# design.net
KiCad netlist of a schematic drawn in Altium Designer
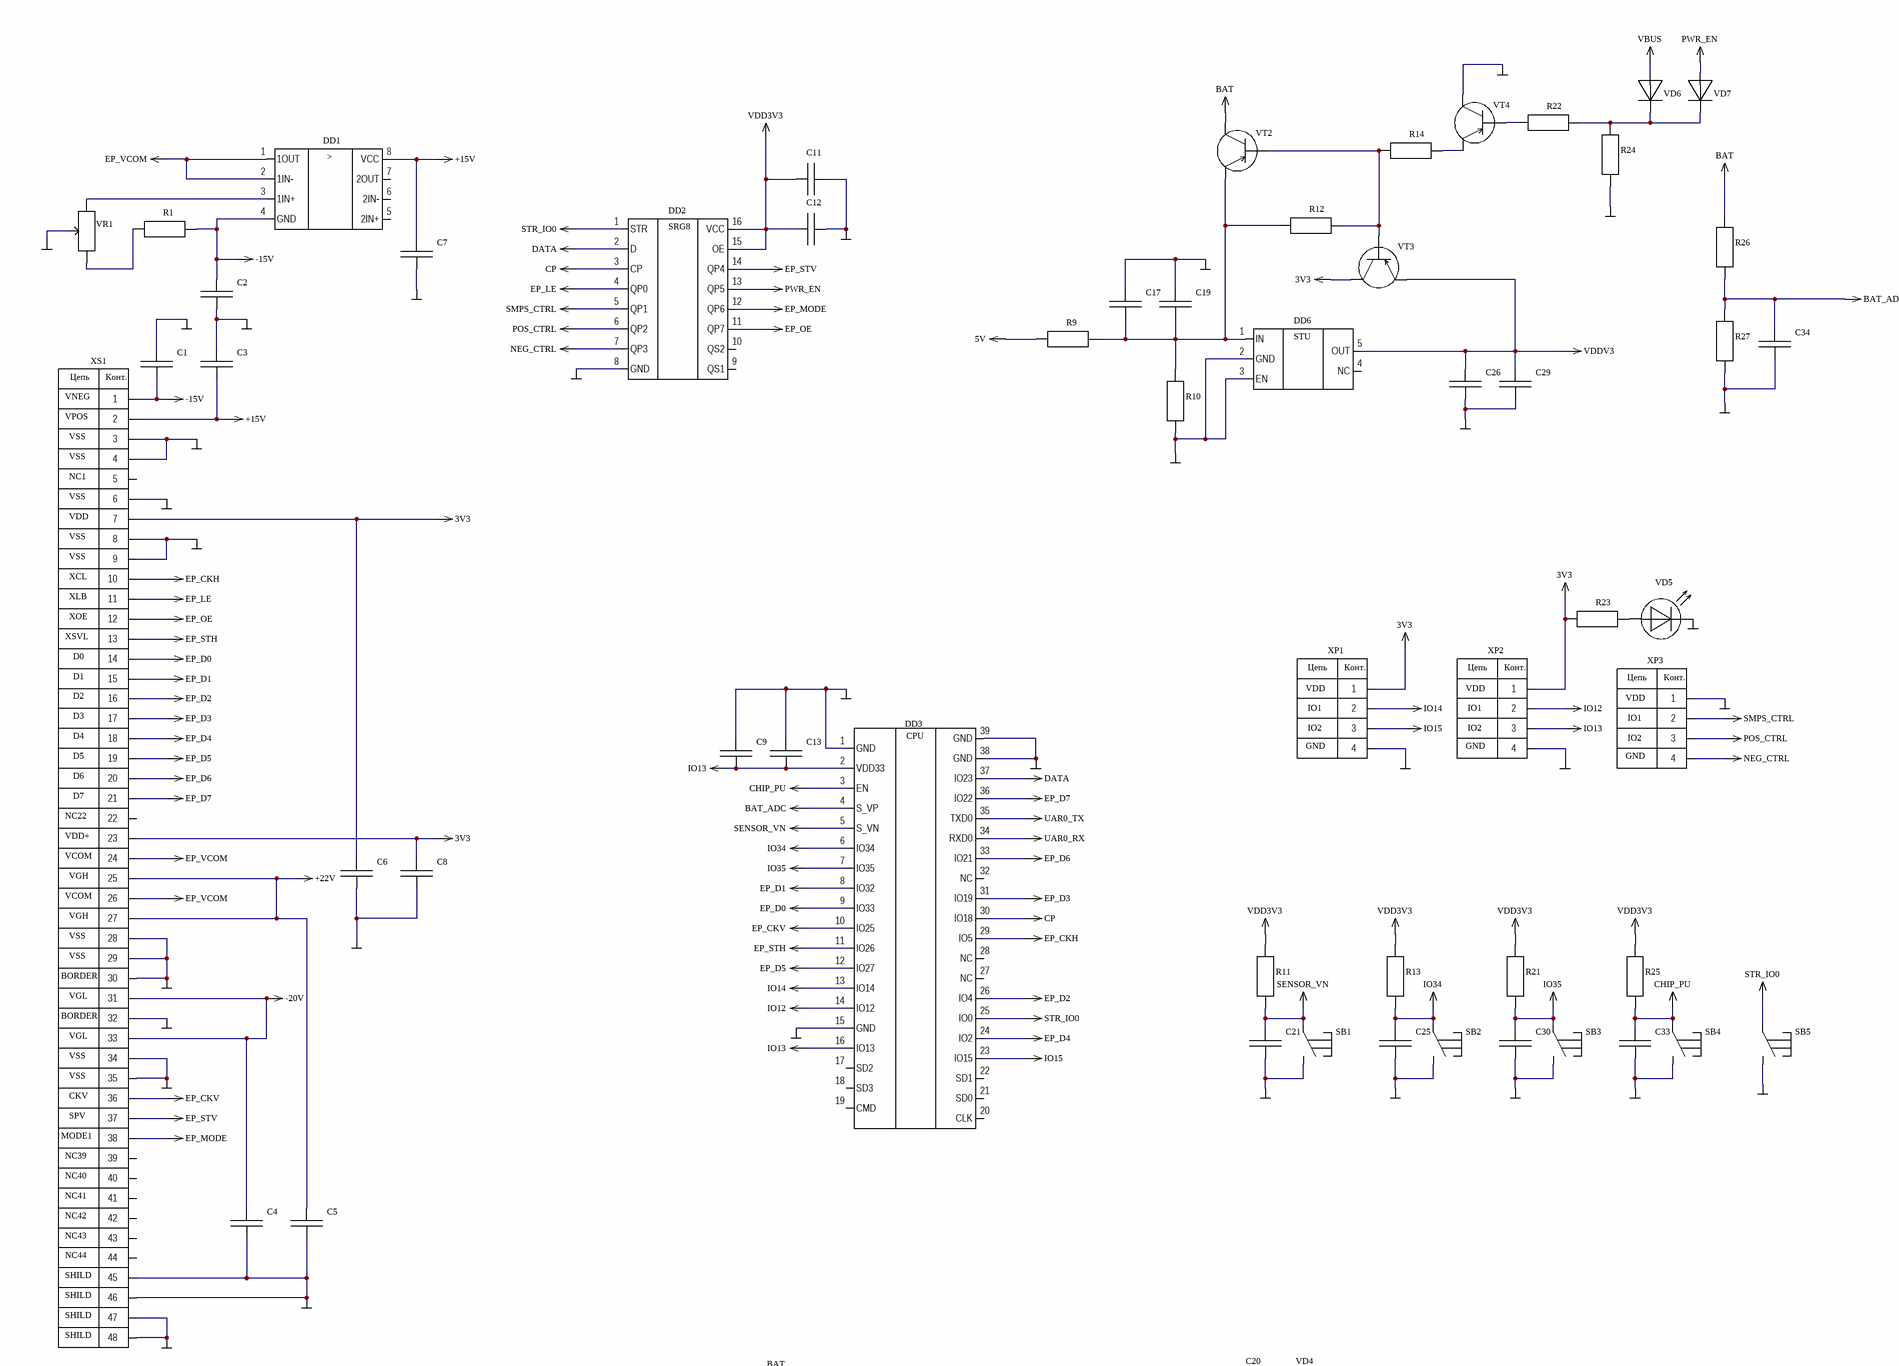
[diagram p0: принципиальная.schdoc, top left]
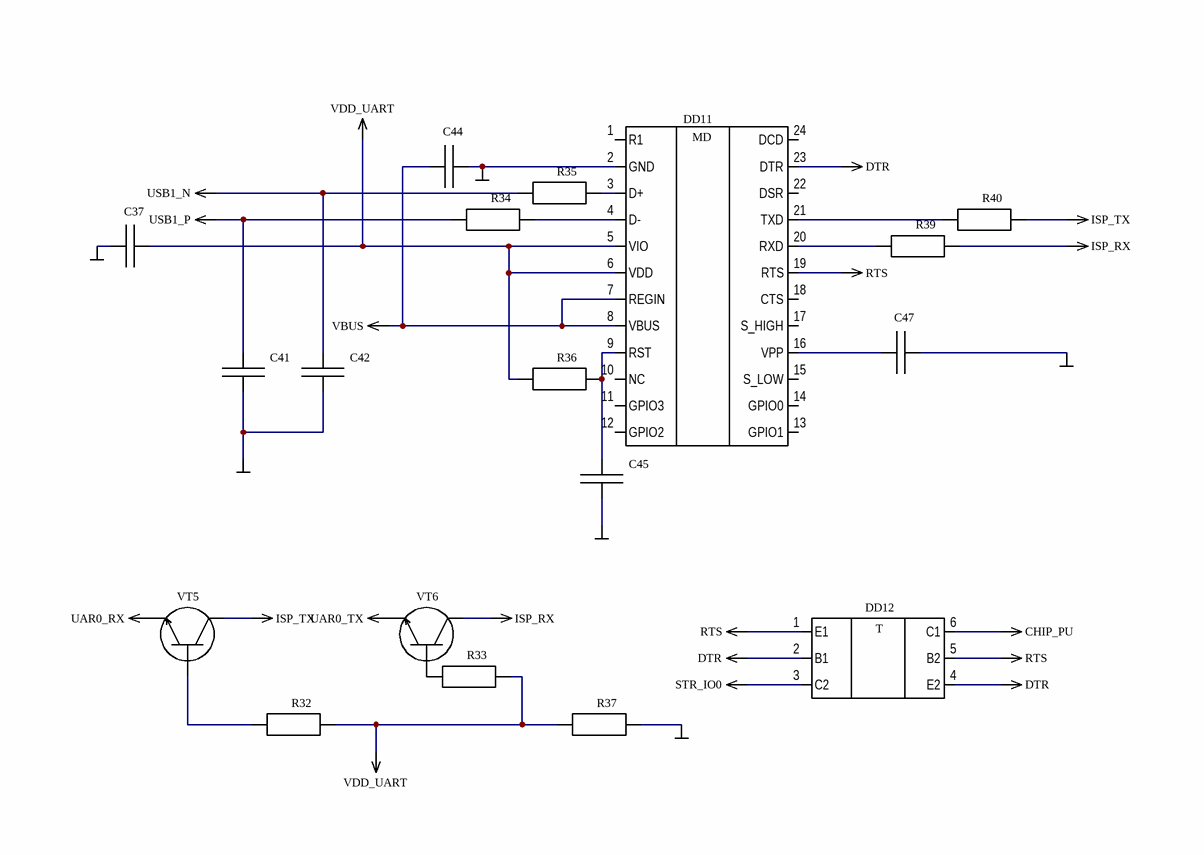
[diagram p1: принципиальная.schdoc, top right]
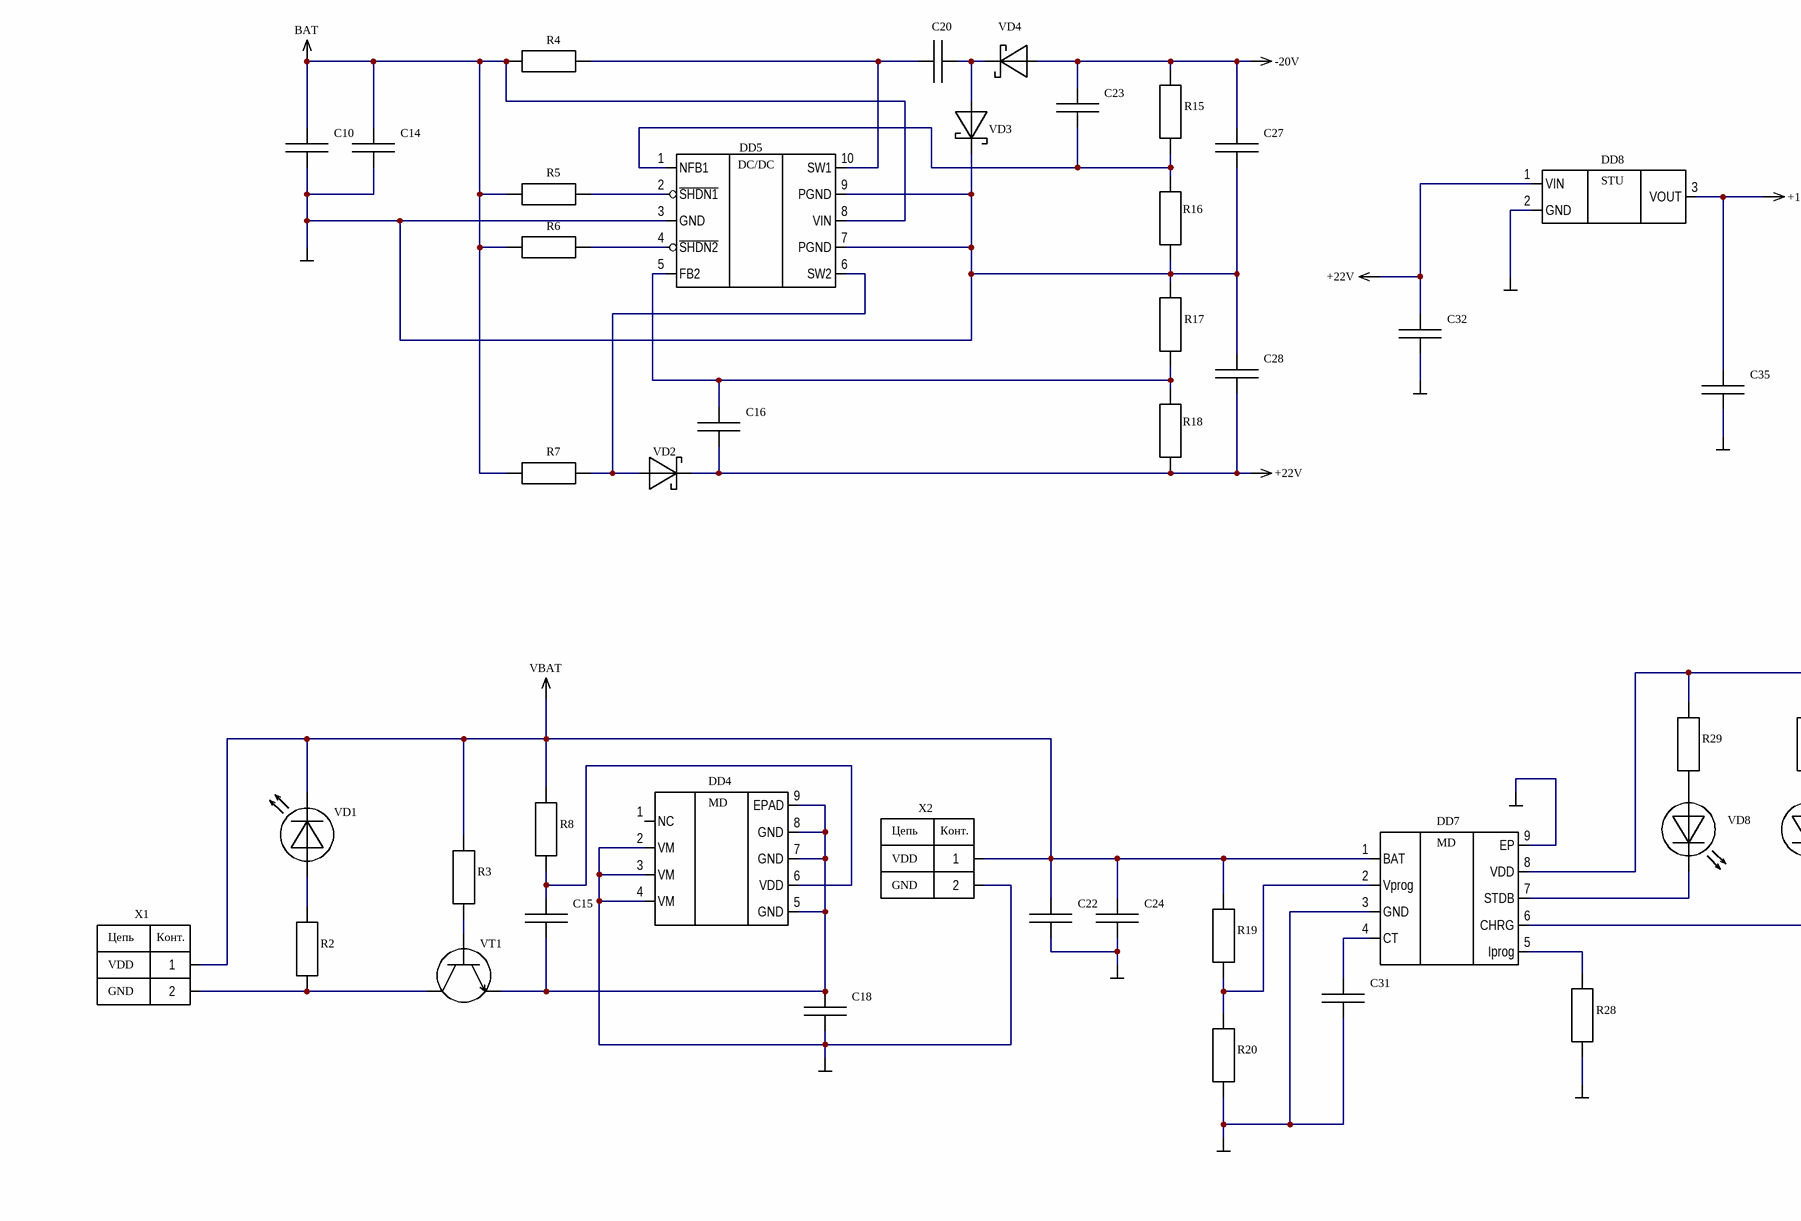
[diagram p2: принципиальная.schdoc, bottom left]
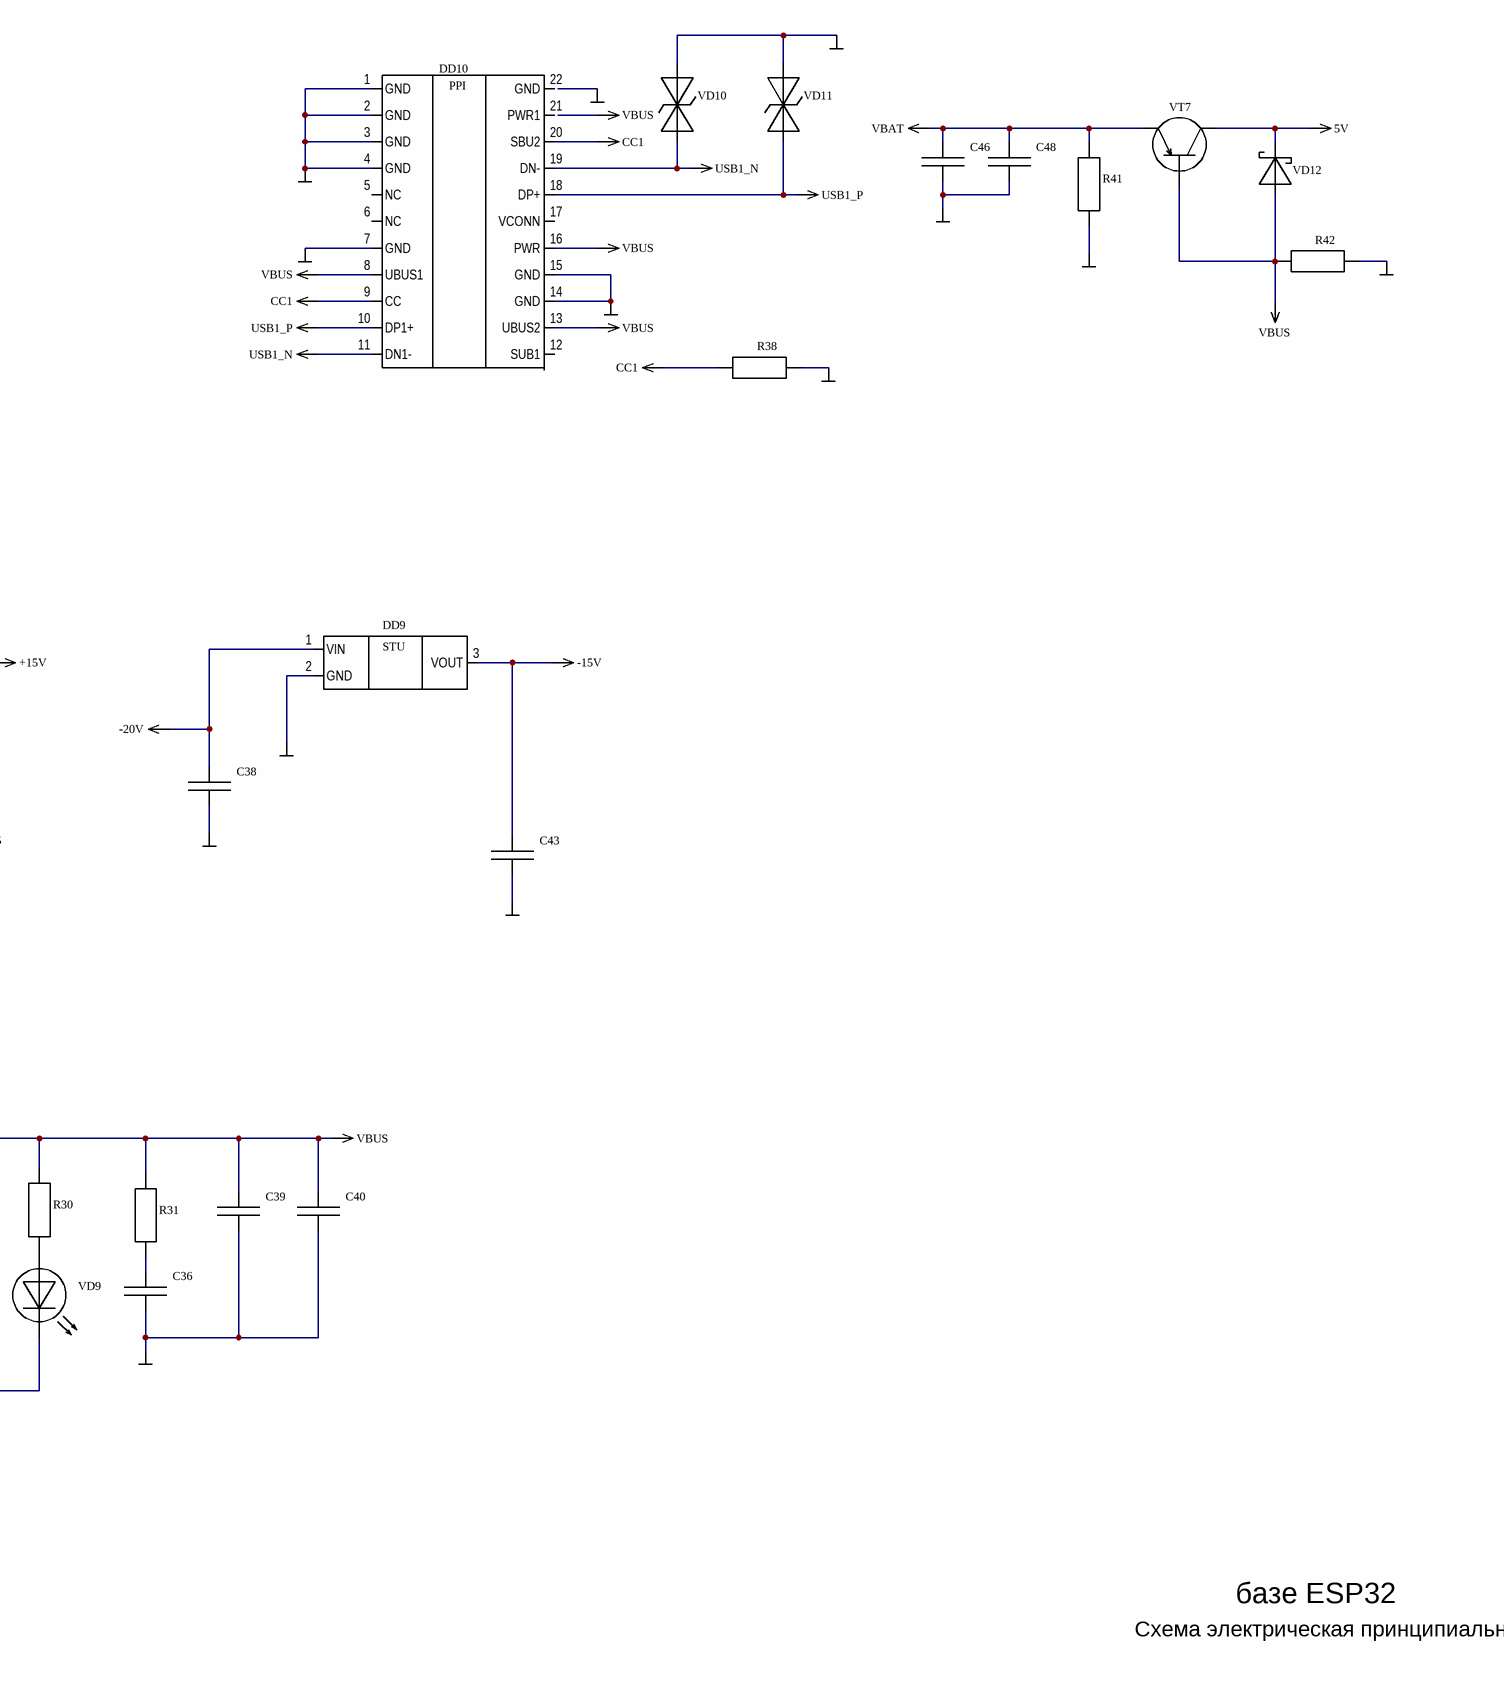
[diagram p3: принципиальная.schdoc, bottom right]

(export (version "E")
  (design (tool "Eeschema 10.0.6"))
  (components
    (comp (ref "C1")
      (value "Capacitor")
      (footprint "condensator CAP3216X125N:CAP3216X125N")
      (libsource (lib "Library_ugo") (part "Capacitor"))
    )
    (comp (ref "C2")
      (value "Capacitor")
      (footprint "condensator CAP3216X125N:CAP3216X125N")
      (libsource (lib "Library_ugo") (part "Capacitor"))
    )
    (comp (ref "C3")
      (value "Capacitor")
      (footprint "condensator CAP3216X125N:CAP3216X125N")
      (libsource (lib "Library_ugo") (part "Capacitor"))
    )
    (comp (ref "C4")
      (value "Capacitor")
      (footprint "condensator CAP3216X125N:CAP3216X125N")
      (libsource (lib "Library_ugo") (part "Capacitor"))
    )
    (comp (ref "C5")
      (value "Capacitor")
      (footprint "condensator CAP3216X125N:CAP3216X125N")
      (libsource (lib "Library_ugo") (part "Capacitor"))
    )
    (comp (ref "C6")
      (value "Capacitor")
      (footprint "condensator CAP3216X125N:CAP3216X125N")
      (libsource (lib "Library_ugo") (part "Capacitor"))
    )
    (comp (ref "C7")
      (value "Capacitor")
      (footprint "condensator CAP3216X125N:CAP3216X125N")
      (libsource (lib "Library_ugo") (part "Capacitor"))
    )
    (comp (ref "C8")
      (value "Capacitor")
      (footprint "condensator CAP3216X125N:CAP3216X125N")
      (libsource (lib "Library_ugo") (part "Capacitor"))
    )
    (comp (ref "C9")
      (value "Capacitor")
      (footprint "condensator CAP3216X125N:CAP3216X125N")
      (libsource (lib "Library_ugo") (part "Capacitor"))
    )
    (comp (ref "C10")
      (value "Capacitor")
      (footprint "condensator CAP3216X125N:CAP3216X125N")
      (libsource (lib "Library_ugo") (part "Capacitor"))
    )
    (comp (ref "C11")
      (value "Capacitor")
      (footprint "condensator CAP3216X125N:CAP3216X125N")
      (libsource (lib "Library_ugo") (part "Capacitor"))
    )
    (comp (ref "C12")
      (value "Capacitor")
      (footprint "condensator CAP3216X125N:CAP3216X125N")
      (libsource (lib "Library_ugo") (part "Capacitor"))
    )
    (comp (ref "C13")
      (value "Capacitor")
      (footprint "condensator CAP3216X125N:CAP3216X125N")
      (libsource (lib "Library_ugo") (part "Capacitor"))
    )
    (comp (ref "C14")
      (value "Capacitor")
      (footprint "condensator CAP3216X125N:CAP3216X125N")
      (libsource (lib "Library_ugo") (part "Capacitor"))
    )
    (comp (ref "C15")
      (value "Capacitor")
      (footprint "condensator CAP3216X125N:CAP3216X125N")
      (libsource (lib "Library_ugo") (part "Capacitor"))
    )
    (comp (ref "C16")
      (value "Capacitor")
      (footprint "condensator CAP3216X125N:CAP3216X125N")
      (libsource (lib "Library_ugo") (part "Capacitor"))
    )
    (comp (ref "C17")
      (value "Capacitor")
      (footprint "condensator CAP3216X125N:CAP3216X125N")
      (libsource (lib "Library_ugo") (part "Capacitor"))
    )
    (comp (ref "C18")
      (value "Capacitor")
      (footprint "condensator CAP3216X125N:CAP3216X125N")
      (libsource (lib "Library_ugo") (part "Capacitor"))
    )
    (comp (ref "C19")
      (value "Capacitor")
      (footprint "condensator CAP3216X125N:CAP3216X125N")
      (libsource (lib "Library_ugo") (part "Capacitor"))
    )
    (comp (ref "C20")
      (value "Capacitor")
      (footprint "condensator CAP3216X125N:CAP3216X125N")
      (libsource (lib "Library_ugo") (part "Capacitor"))
    )
    (comp (ref "C21")
      (value "Capacitor")
      (footprint "condensator CAP3216X125N:CAP3216X125N")
      (libsource (lib "Library_ugo") (part "Capacitor"))
    )
    (comp (ref "C22")
      (value "Capacitor")
      (footprint "condensator CAP3216X125N:CAP3216X125N")
      (libsource (lib "Library_ugo") (part "Capacitor"))
    )
    (comp (ref "C23")
      (value "Capacitor")
      (footprint "condensator CAP3216X125N:CAP3216X125N")
      (libsource (lib "Library_ugo") (part "Capacitor"))
    )
    (comp (ref "C24")
      (value "Capacitor")
      (footprint "condensator CAP3216X125N:CAP3216X125N")
      (libsource (lib "Library_ugo") (part "Capacitor"))
    )
    (comp (ref "C25")
      (value "Capacitor")
      (footprint "condensator CAP3216X125N:CAP3216X125N")
      (libsource (lib "Library_ugo") (part "Capacitor"))
    )
    (comp (ref "C26")
      (value "Capacitor")
      (footprint "condensator CAP3216X125N:CAP3216X125N")
      (libsource (lib "Library_ugo") (part "Capacitor"))
    )
    (comp (ref "C27")
      (value "Capacitor")
      (footprint "condensator CAP3216X125N:CAP3216X125N")
      (libsource (lib "Library_ugo") (part "Capacitor"))
    )
    (comp (ref "C28")
      (value "Capacitor")
      (footprint "condensator CAP3216X125N:CAP3216X125N")
      (libsource (lib "Library_ugo") (part "Capacitor"))
    )
    (comp (ref "C29")
      (value "Capacitor")
      (footprint "condensator CAP3216X125N:CAP3216X125N")
      (libsource (lib "Library_ugo") (part "Capacitor"))
    )
    (comp (ref "C30")
      (value "Capacitor")
      (footprint "condensator CAP3216X125N:CAP3216X125N")
      (libsource (lib "Library_ugo") (part "Capacitor"))
    )
    (comp (ref "C31")
      (value "Capacitor")
      (footprint "condensator CAP3216X125N:CAP3216X125N")
      (libsource (lib "Library_ugo") (part "Capacitor"))
    )
    (comp (ref "C32")
      (value "Capacitor")
      (footprint "condensator CAP3216X125N:CAP3216X125N")
      (libsource (lib "Library_ugo") (part "Capacitor"))
    )
    (comp (ref "C33")
      (value "Capacitor")
      (footprint "condensator CAP3216X125N:CAP3216X125N")
      (libsource (lib "Library_ugo") (part "Capacitor"))
    )
    (comp (ref "C34")
      (value "Capacitor")
      (footprint "condensator CAP3216X125N:CAP3216X125N")
      (libsource (lib "Library_ugo") (part "Capacitor"))
    )
    (comp (ref "C35")
      (value "Capacitor")
      (footprint "condensator CAP3216X125N:CAP3216X125N")
      (libsource (lib "Library_ugo") (part "Capacitor"))
    )
    (comp (ref "C36")
      (value "Capacitor")
      (footprint "condensator CAP3216X125N:CAP3216X125N")
      (libsource (lib "Library_ugo") (part "Capacitor"))
    )
    (comp (ref "C37")
      (value "Capacitor")
      (footprint "condensator CAP3216X125N:CAP3216X125N")
      (libsource (lib "Library_ugo") (part "Capacitor"))
    )
    (comp (ref "C38")
      (value "Capacitor")
      (footprint "condensator CAP3216X125N:CAP3216X125N")
      (libsource (lib "Library_ugo") (part "Capacitor"))
    )
    (comp (ref "C39")
      (value "Capacitor")
      (footprint "condensator CAP3216X125N:CAP3216X125N")
      (libsource (lib "Library_ugo") (part "Capacitor"))
    )
    (comp (ref "C40")
      (value "Capacitor")
      (footprint "condensator CAP3216X125N:CAP3216X125N")
      (libsource (lib "Library_ugo") (part "Capacitor"))
    )
    (comp (ref "C41")
      (value "Capacitor")
      (footprint "condensator CAP3216X125N:CAP3216X125N")
      (libsource (lib "Library_ugo") (part "Capacitor"))
    )
    (comp (ref "C42")
      (value "Capacitor")
      (footprint "condensator CAP3216X125N:CAP3216X125N")
      (libsource (lib "Library_ugo") (part "Capacitor"))
    )
    (comp (ref "C43")
      (value "Capacitor")
      (footprint "condensator CAP3216X125N:CAP3216X125N")
      (libsource (lib "Library_ugo") (part "Capacitor"))
    )
    (comp (ref "C44")
      (value "Capacitor")
      (footprint "condensator CAP3216X125N:CAP3216X125N")
      (libsource (lib "Library_ugo") (part "Capacitor"))
    )
    (comp (ref "C45")
      (value "Capacitor")
      (footprint "condensator CAP3216X125N:CAP3216X125N")
      (libsource (lib "Library_ugo") (part "Capacitor"))
    )
    (comp (ref "C46")
      (value "Capacitor")
      (footprint "condensator CAP3216X125N:CAP3216X125N")
      (libsource (lib "Library_ugo") (part "Capacitor"))
    )
    (comp (ref "C47")
      (value "Capacitor")
      (footprint "condensator CAP3216X125N:CAP3216X125N")
      (libsource (lib "Library_ugo") (part "Capacitor"))
    )
    (comp (ref "C48")
      (value "Capacitor")
      (footprint "condensator CAP3216X125N:CAP3216X125N")
      (libsource (lib "Library_ugo") (part "Capacitor"))
    )
    (comp (ref "DD1")
      (value "LM358DR2G")
      (footprint "SOIC127P599X175-8N:SOIC127P599X175-8N")
      (libsource (lib "Library_ugo") (part "LM358DR2G"))
    )
    (comp (ref "DD2")
      (value "74HCT4094D")
      (footprint "SOIC127P1030X265-16N:SOIC127P1030X265-16N")
      (libsource (lib "Library_ugo") (part "74HCT4094D"))
    )
    (comp (ref "DD3")
      (value "ESP32-WROVER-E")
      (footprint "SnapEDApcb:XCVR_ESP32-WROVER")
      (libsource (lib "Library_ugo") (part "ESP32-WROVER-E"))
    )
    (comp (ref "DD4")
      (value "IP3005A")
      (footprint "SI2301:ESOP-8_L4.9-W3.9-P1.27-LS6.0-BL-EP")
      (libsource (lib "Library_ugo") (part "IP3005A"))
    )
    (comp (ref "DD5")
      (value "LT1945")
      (footprint "MSOP-10_MS:MSOP-10_MS")
      (libsource (lib "Library_ugo") (part "LT1945"))
    )
    (comp (ref "DD6")
      (value "AP2112K")
      (footprint "SnapEDApcb:SOT95P280X145-5N")
      (libsource (lib "Library_ugo") (part "AP2112K"))
    )
    (comp (ref "DD7")
      (value "HX6610S")
      (footprint "SI2301:ESOP-8_L4.9-W3.9-P1.27-LS6.0-BL-EP")
      (libsource (lib "Library_ugo") (part "HX6610S"))
    )
    (comp (ref "DD8")
      (value "CJ78L15")
      (footprint "SnapEDApcb:REG_MCP1702T-3302E/MB")
      (libsource (lib "Library_ugo") (part "CJ78L15"))
    )
    (comp (ref "DD9")
      (value "CJ78L15")
      (footprint "SnapEDApcb:REG_MCP1702T-3302E/MB")
      (libsource (lib "Library_ugo") (part "CJ78L15"))
    )
    (comp (ref "DD10")
      (value "TYPE C")
      (footprint "SnapEDApcb:QFN50P400X400X80-25N")
      (libsource (lib "Library_ugo") (part "TYPE C"))
    )
    (comp (ref "DD11")
      (value "CP2014")
      (footprint "SnapEDApcb:QFN50P400X400X80-25N")
      (libsource (lib "Library_ugo") (part "CP2014"))
    )
    (comp (ref "DD12")
      (value "UMH3N")
      (footprint "SnapEDApcb:SOP65P210X100-6N")
      (libsource (lib "Library_ugo") (part "UMH3N"))
    )
    (comp (ref "R1")
      (value "Resistor")
      (footprint "Library_footprint:res0603")
      (libsource (lib "Library_ugo") (part "Resistor"))
    )
    (comp (ref "R2")
      (value "Resistor")
      (footprint "Library_footprint:res0603")
      (libsource (lib "Library_ugo") (part "Resistor"))
    )
    (comp (ref "R3")
      (value "Resistor")
      (footprint "Library_footprint:res0603")
      (libsource (lib "Library_ugo") (part "Resistor"))
    )
    (comp (ref "R4")
      (value "Resistor")
      (footprint "Library_footprint:res0603")
      (libsource (lib "Library_ugo") (part "Resistor"))
    )
    (comp (ref "R5")
      (value "Resistor")
      (footprint "Library_footprint:res0603")
      (libsource (lib "Library_ugo") (part "Resistor"))
    )
    (comp (ref "R6")
      (value "Resistor")
      (footprint "Library_footprint:res0603")
      (libsource (lib "Library_ugo") (part "Resistor"))
    )
    (comp (ref "R7")
      (value "Resistor")
      (footprint "Library_footprint:res0603")
      (libsource (lib "Library_ugo") (part "Resistor"))
    )
    (comp (ref "R8")
      (value "Resistor")
      (footprint "Library_footprint:res0603")
      (libsource (lib "Library_ugo") (part "Resistor"))
    )
    (comp (ref "R9")
      (value "Resistor")
      (footprint "Library_footprint:res0603")
      (libsource (lib "Library_ugo") (part "Resistor"))
    )
    (comp (ref "R10")
      (value "Resistor")
      (footprint "Library_footprint:res0603")
      (libsource (lib "Library_ugo") (part "Resistor"))
    )
    (comp (ref "R11")
      (value "Resistor")
      (footprint "Library_footprint:res0603")
      (libsource (lib "Library_ugo") (part "Resistor"))
    )
    (comp (ref "R12")
      (value "Resistor")
      (footprint "Library_footprint:res0603")
      (libsource (lib "Library_ugo") (part "Resistor"))
    )
    (comp (ref "R13")
      (value "Resistor")
      (footprint "Library_footprint:res0603")
      (libsource (lib "Library_ugo") (part "Resistor"))
    )
    (comp (ref "R14")
      (value "Resistor")
      (footprint "Library_footprint:res0603")
      (libsource (lib "Library_ugo") (part "Resistor"))
    )
    (comp (ref "R15")
      (value "Resistor")
      (footprint "Library_footprint:res0603")
      (libsource (lib "Library_ugo") (part "Resistor"))
    )
    (comp (ref "R16")
      (value "Resistor")
      (footprint "Library_footprint:res0603")
      (libsource (lib "Library_ugo") (part "Resistor"))
    )
    (comp (ref "R17")
      (value "Resistor")
      (footprint "Library_footprint:res0603")
      (libsource (lib "Library_ugo") (part "Resistor"))
    )
    (comp (ref "R18")
      (value "Resistor")
      (footprint "Library_footprint:res0603")
      (libsource (lib "Library_ugo") (part "Resistor"))
    )
    (comp (ref "R19")
      (value "Resistor")
      (footprint "Library_footprint:res0603")
      (libsource (lib "Library_ugo") (part "Resistor"))
    )
    (comp (ref "R20")
      (value "Resistor")
      (footprint "Library_footprint:res0603")
      (libsource (lib "Library_ugo") (part "Resistor"))
    )
    (comp (ref "R21")
      (value "Resistor")
      (footprint "Library_footprint:res0603")
      (libsource (lib "Library_ugo") (part "Resistor"))
    )
    (comp (ref "R22")
      (value "Resistor")
      (footprint "Library_footprint:res0603")
      (libsource (lib "Library_ugo") (part "Resistor"))
    )
    (comp (ref "R23")
      (value "Resistor")
      (footprint "Library_footprint:res0603")
      (libsource (lib "Library_ugo") (part "Resistor"))
    )
    (comp (ref "R24")
      (value "Resistor")
      (footprint "Library_footprint:res0603")
      (libsource (lib "Library_ugo") (part "Resistor"))
    )
    (comp (ref "R25")
      (value "Resistor")
      (footprint "Library_footprint:res0603")
      (libsource (lib "Library_ugo") (part "Resistor"))
    )
    (comp (ref "R26")
      (value "Resistor")
      (footprint "Library_footprint:res0603")
      (libsource (lib "Library_ugo") (part "Resistor"))
    )
    (comp (ref "R27")
      (value "Resistor")
      (footprint "Library_footprint:res0603")
      (libsource (lib "Library_ugo") (part "Resistor"))
    )
    (comp (ref "R28")
      (value "Resistor")
      (footprint "Library_footprint:res0603")
      (libsource (lib "Library_ugo") (part "Resistor"))
    )
    (comp (ref "R29")
      (value "Resistor")
      (footprint "Library_footprint:res0603")
      (libsource (lib "Library_ugo") (part "Resistor"))
    )
    (comp (ref "R30")
      (value "Resistor")
      (footprint "Library_footprint:res0603")
      (libsource (lib "Library_ugo") (part "Resistor"))
    )
    (comp (ref "R31")
      (value "Resistor")
      (footprint "Library_footprint:res0603")
      (libsource (lib "Library_ugo") (part "Resistor"))
    )
    (comp (ref "R32")
      (value "Resistor")
      (footprint "Library_footprint:res0603")
      (libsource (lib "Library_ugo") (part "Resistor"))
    )
    (comp (ref "R33")
      (value "Resistor")
      (footprint "Library_footprint:res0603")
      (libsource (lib "Library_ugo") (part "Resistor"))
    )
    (comp (ref "R34")
      (value "Resistor")
      (footprint "Library_footprint:res0603")
      (libsource (lib "Library_ugo") (part "Resistor"))
    )
    (comp (ref "R35")
      (value "Resistor")
      (footprint "Library_footprint:res0603")
      (libsource (lib "Library_ugo") (part "Resistor"))
    )
    (comp (ref "R36")
      (value "Resistor")
      (footprint "Library_footprint:res0603")
      (libsource (lib "Library_ugo") (part "Resistor"))
    )
    (comp (ref "R37")
      (value "Resistor")
      (footprint "Library_footprint:res0603")
      (libsource (lib "Library_ugo") (part "Resistor"))
    )
    (comp (ref "R38")
      (value "Resistor")
      (footprint "Library_footprint:res0603")
      (libsource (lib "Library_ugo") (part "Resistor"))
    )
    (comp (ref "R39")
      (value "Resistor")
      (footprint "Library_footprint:res0603")
      (libsource (lib "Library_ugo") (part "Resistor"))
    )
    (comp (ref "R40")
      (value "Resistor")
      (footprint "Library_footprint:res0603")
      (libsource (lib "Library_ugo") (part "Resistor"))
    )
    (comp (ref "R41")
      (value "Resistor")
      (footprint "Library_footprint:res0603")
      (libsource (lib "Library_ugo") (part "Resistor"))
    )
    (comp (ref "R42")
      (value "Resistor")
      (footprint "Library_footprint:res0603")
      (libsource (lib "Library_ugo") (part "Resistor"))
    )
    (comp (ref "SB1")
      (value "button")
      (footprint "SnapEDApcb:SW_147873-1")
      (libsource (lib "Library_ugo") (part "button"))
    )
    (comp (ref "SB2")
      (value "button")
      (footprint "SnapEDApcb:SW_147873-1")
      (libsource (lib "Library_ugo") (part "button"))
    )
    (comp (ref "SB3")
      (value "button")
      (footprint "SnapEDApcb:SW_147873-1")
      (libsource (lib "Library_ugo") (part "button"))
    )
    (comp (ref "SB4")
      (value "button")
      (footprint "SnapEDApcb:SW_147873-1")
      (libsource (lib "Library_ugo") (part "button"))
    )
    (comp (ref "SB5")
      (value "button")
      (footprint "SnapEDApcb:SW_147873-1")
      (libsource (lib "Library_ugo") (part "button"))
    )
    (comp (ref "VD1")
      (value "LED diode")
      (footprint "led diode:BEADC0603X33N")
      (libsource (lib "Library_ugo") (part "LED diode"))
    )
    (comp (ref "VD2")
      (value "1N5819")
      (footprint "SOD3715X145N:SOD3715X145N")
      (libsource (lib "Library_ugo") (part "1N5819"))
    )
    (comp (ref "VD3")
      (value "1N5819")
      (footprint "SOD3715X145N:SOD3715X145N")
      (libsource (lib "Library_ugo") (part "1N5819"))
    )
    (comp (ref "VD4")
      (value "1N5819")
      (footprint "SOD3715X145N:SOD3715X145N")
      (libsource (lib "Library_ugo") (part "1N5819"))
    )
    (comp (ref "VD5")
      (value "LED diode")
      (footprint "led diode:BEADC0603X33N")
      (libsource (lib "Library_ugo") (part "LED diode"))
    )
    (comp (ref "VD6")
      (value "Diod")
      (footprint "SnapEDApcb:SODFL1608X70N")
      (libsource (lib "Library_ugo") (part "Diod"))
    )
    (comp (ref "VD7")
      (value "Diod")
      (footprint "SnapEDApcb:SODFL1608X70N")
      (libsource (lib "Library_ugo") (part "Diod"))
    )
    (comp (ref "VD8")
      (value "LED diode")
      (footprint "led diode:BEADC0603X33N")
      (libsource (lib "Library_ugo") (part "LED diode"))
    )
    (comp (ref "VD9")
      (value "LED diode")
      (footprint "led diode:BEADC0603X33N")
      (libsource (lib "Library_ugo") (part "LED diode"))
    )
    (comp (ref "VD10")
      (value "ESD diode")
      (footprint "SnapEDApcb:SOD523")
      (libsource (lib "Library_ugo") (part "ESD diode"))
    )
    (comp (ref "VD11")
      (value "ESD diode")
      (footprint "SnapEDApcb:SOD523")
      (libsource (lib "Library_ugo") (part "ESD diode"))
    )
    (comp (ref "VD12")
      (value "1N5819")
      (footprint "SOD3715X145N:SOD3715X145N")
      (libsource (lib "Library_ugo") (part "1N5819"))
    )
    (comp (ref "VR1")
      (value "TRIMPOT-SMD-3MM")
      (footprint "SOIC127P599X175-8N:TRIMPOT-SMD-TC33X")
      (libsource (lib "Library_ugo") (part "TRIMPOT-SMD-3MM"))
    )
    (comp (ref "VT1")
      (value "Transistor(npn)")
      (footprint "SI2301:SOT23-3P96_237X112L42X44")
      (libsource (lib "Library_ugo") (part "Transistor(npn)"))
    )
    (comp (ref "VT2")
      (value "Transistor(pnp)")
      (footprint "SI2301:SOT23-3P96_237X112L42X44")
      (libsource (lib "Library_ugo") (part "Transistor(pnp)"))
    )
    (comp (ref "VT3")
      (value "Transistor(pnp)")
      (footprint "SI2301:SOT23-3P96_237X112L42X44")
      (libsource (lib "Library_ugo") (part "Transistor(pnp)"))
    )
    (comp (ref "VT4")
      (value "Transistor(pnp)")
      (footprint "SI2301:SOT23-3P96_237X112L42X44")
      (libsource (lib "Library_ugo") (part "Transistor(pnp)"))
    )
    (comp (ref "VT5")
      (value "Transistor(npn)")
      (footprint "SI2301:SOT23-3P96_237X112L42X44")
      (libsource (lib "Library_ugo") (part "Transistor(npn)"))
    )
    (comp (ref "VT6")
      (value "Transistor(npn)")
      (footprint "SI2301:SOT23-3P96_237X112L42X44")
      (libsource (lib "Library_ugo") (part "Transistor(npn)"))
    )
    (comp (ref "VT7")
      (value "Transistor(pnp)")
      (footprint "SI2301:SOT23-3P96_237X112L42X44")
      (libsource (lib "Library_ugo") (part "Transistor(pnp)"))
    )
    (comp (ref "X1") (value "2P") (footprint "SI2301:2P") (libsource (lib "Library_ugo") (part "2P")))
    (comp (ref "X2") (value "2P") (footprint "SI2301:2P") (libsource (lib "Library_ugo") (part "2P")))
    (comp (ref "XP1")
      (value "MOLEX P4")
      (footprint "SnapEDApcb:MOLEX_15244441")
      (libsource (lib "Library_ugo") (part "MOLEX P4"))
    )
    (comp (ref "XP2")
      (value "MOLEX P4")
      (footprint "SnapEDApcb:MOLEX_15244441")
      (libsource (lib "Library_ugo") (part "MOLEX P4"))
    )
    (comp (ref "XP3")
      (value "MOLEX P4")
      (footprint "SnapEDApcb:MOLEX_15244441")
      (libsource (lib "Library_ugo") (part "MOLEX P4"))
    )
    (comp (ref "XS1")
      (value "DVI")
      (footprint "GCT_FFC2B28-22-G_REVA:GCT_FFC2B28-22-G_REVA")
      (libsource (lib "Library_ugo") (part "DVI"))
    )
  )
  (nets
    (net (code "1") (name "+15V") (class "Default")
      (node (ref "C3") (pin "2") (pinfunction "A_2") (pintype "passive"))
      (node (ref "C35") (pin "1") (pinfunction "A_1") (pintype "passive"))
      (node (ref "C7") (pin "1") (pinfunction "A_1") (pintype "passive"))
      (node (ref "DD1") (pin "8") (pinfunction "VCC_8") (pintype "passive"))
      (node (ref "DD8") (pin "3") (pinfunction "VOUT_3") (pintype "passive"))
      (node (ref "XS1") (pin "2") (pinfunction "2_2") (pintype "passive"))
    )
    (net (code "2") (name "+22V") (class "Default")
      (node (ref "C16") (pin "2") (pinfunction "A_2") (pintype "passive"))
      (node (ref "C28") (pin "2") (pinfunction "A_2") (pintype "passive"))
      (node (ref "C32") (pin "1") (pinfunction "A_1") (pintype "passive"))
      (node (ref "C5") (pin "1") (pinfunction "A_1") (pintype "passive"))
      (node (ref "DD8") (pin "1") (pinfunction "VIN_1") (pintype "passive"))
      (node (ref "R18") (pin "1") (pinfunction "A_1") (pintype "passive"))
      (node (ref "VD2") (pin "2") (pinfunction "B_2") (pintype "passive"))
      (node (ref "XS1") (pin "25") (pinfunction "25_25") (pintype "passive"))
      (node (ref "XS1") (pin "27") (pinfunction "27_27") (pintype "passive"))
    )
    (net (code "3") (name "-15V") (class "Default")
      (node (ref "C1") (pin "2") (pinfunction "A_2") (pintype "passive"))
      (node (ref "C2") (pin "1") (pinfunction "A_1") (pintype "passive"))
      (node (ref "C43") (pin "1") (pinfunction "A_1") (pintype "passive"))
      (node (ref "DD1") (pin "4") (pinfunction "GND_4") (pintype "passive"))
      (node (ref "DD9") (pin "3") (pinfunction "VOUT_3") (pintype "passive"))
      (node (ref "R1") (pin "2") (pinfunction "B_2") (pintype "passive"))
      (node (ref "XS1") (pin "1") (pinfunction "1_1") (pintype "passive"))
    )
    (net (code "4") (name "-20V") (class "Default")
      (node (ref "C23") (pin "1") (pinfunction "A_1") (pintype "passive"))
      (node (ref "C27") (pin "1") (pinfunction "A_1") (pintype "passive"))
      (node (ref "C38") (pin "1") (pinfunction "A_1") (pintype "passive"))
      (node (ref "C4") (pin "1") (pinfunction "A_1") (pintype "passive"))
      (node (ref "DD9") (pin "1") (pinfunction "VIN_1") (pintype "passive"))
      (node (ref "R15") (pin "2") (pinfunction "B_2") (pintype "passive"))
      (node (ref "VD4") (pin "1") (pinfunction "A_1") (pintype "passive"))
      (node (ref "XS1") (pin "31") (pinfunction "31_31") (pintype "passive"))
      (node (ref "XS1") (pin "33") (pinfunction "33_33") (pintype "passive"))
    )
    (net (code "5") (name "3V3") (class "Default")
      (node (ref "C6") (pin "1") (pinfunction "A_1") (pintype "passive"))
      (node (ref "C8") (pin "1") (pinfunction "A_1") (pintype "passive"))
      (node (ref "R23") (pin "1") (pinfunction "A_1") (pintype "passive"))
      (node (ref "VT3") (pin "2") (pinfunction "B_2") (pintype "passive"))
      (node (ref "XP1") (pin "1") (pinfunction "1_1") (pintype "passive"))
      (node (ref "XP2") (pin "1") (pinfunction "1_1") (pintype "passive"))
      (node (ref "XS1") (pin "23") (pinfunction "23_23") (pintype "passive"))
      (node (ref "XS1") (pin "7") (pinfunction "7_7") (pintype "passive"))
    )
    (net (code "6") (name "5V") (class "Default")
      (node (ref "R9") (pin "1") (pinfunction "A_1") (pintype "passive"))
      (node (ref "VD12") (pin "2") (pinfunction "B_2") (pintype "passive"))
      (node (ref "VT7") (pin "2") (pinfunction "B_2") (pintype "passive"))
    )
    (net (code "7") (name "BAT") (class "Default")
      (node (ref "C10") (pin "1") (pinfunction "A_1") (pintype "passive"))
      (node (ref "C14") (pin "1") (pinfunction "A_1") (pintype "passive"))
      (node (ref "DD5") (pin "8") (pinfunction "VIN_8") (pintype "passive"))
      (node (ref "R26") (pin "2") (pinfunction "B_2") (pintype "passive"))
      (node (ref "R4") (pin "1") (pinfunction "A_1") (pintype "passive"))
      (node (ref "R5") (pin "1") (pinfunction "A_1") (pintype "passive"))
      (node (ref "R6") (pin "1") (pinfunction "A_1") (pintype "passive"))
      (node (ref "R7") (pin "1") (pinfunction "A_1") (pintype "passive"))
      (node (ref "VT2") (pin "2") (pinfunction "B_2") (pintype "passive"))
    )
    (net (code "8") (name "BAT_ADC") (class "Default")
      (node (ref "C34") (pin "1") (pinfunction "A_1") (pintype "passive"))
      (node (ref "DD3") (pin "4") (pinfunction "S_VP_4") (pintype "passive"))
      (node (ref "R26") (pin "1") (pinfunction "A_1") (pintype "passive"))
      (node (ref "R27") (pin "2") (pinfunction "B_2") (pintype "passive"))
    )
    (net (code "9") (name "CC1") (class "Default")
      (node (ref "DD10") (pin "20") (pinfunction "SBU2_20") (pintype "passive"))
      (node (ref "DD10") (pin "9") (pinfunction "CC_9") (pintype "passive"))
      (node (ref "R38") (pin "1") (pinfunction "A_1") (pintype "passive"))
    )
    (net (code "10") (name "CHIP_PU") (class "Default")
      (node (ref "C33") (pin "2") (pinfunction "A_2") (pintype "passive"))
      (node (ref "DD12") (pin "6") (pinfunction "C1_6") (pintype "passive"))
      (node (ref "DD3") (pin "3") (pinfunction "EN_3") (pintype "passive"))
      (node (ref "R25") (pin "1") (pinfunction "A_1") (pintype "passive"))
      (node (ref "SB4") (pin "1") (pinfunction "1_1") (pintype "passive"))
    )
    (net (code "11") (name "CP") (class "Default")
      (node (ref "DD2") (pin "3") (pinfunction "CP_3") (pintype "passive"))
      (node (ref "DD3") (pin "30") (pinfunction "IO18_30") (pintype "passive"))
    )
    (net (code "12") (name "DATA") (class "Default")
      (node (ref "DD2") (pin "2") (pinfunction "D_2") (pintype "passive"))
      (node (ref "DD3") (pin "37") (pinfunction "IO23_37") (pintype "passive"))
    )
    (net (code "13") (name "DTR") (class "Default")
      (node (ref "DD11") (pin "23") (pinfunction "DTR_23") (pintype "passive"))
      (node (ref "DD12") (pin "2") (pinfunction "B1_2") (pintype "passive"))
      (node (ref "DD12") (pin "4") (pinfunction "E2_4") (pintype "passive"))
    )
    (net (code "14") (name "EP_CKH") (class "Default")
      (node (ref "DD3") (pin "29") (pinfunction "IO5_29") (pintype "passive"))
      (node (ref "XS1") (pin "10") (pinfunction "10_10") (pintype "passive"))
    )
    (net (code "15") (name "EP_CKV") (class "Default")
      (node (ref "DD3") (pin "10") (pinfunction "IO25_10") (pintype "passive"))
      (node (ref "XS1") (pin "36") (pinfunction "36_36") (pintype "passive"))
    )
    (net (code "16") (name "EP_D0") (class "Default")
      (node (ref "DD3") (pin "9") (pinfunction "IO33_9") (pintype "passive"))
      (node (ref "XS1") (pin "14") (pinfunction "14_14") (pintype "passive"))
    )
    (net (code "17") (name "EP_D1") (class "Default")
      (node (ref "DD3") (pin "8") (pinfunction "IO32_8") (pintype "passive"))
      (node (ref "XS1") (pin "15") (pinfunction "15_15") (pintype "passive"))
    )
    (net (code "18") (name "EP_D2") (class "Default")
      (node (ref "DD3") (pin "26") (pinfunction "IO4_26") (pintype "passive"))
      (node (ref "XS1") (pin "16") (pinfunction "16_16") (pintype "passive"))
    )
    (net (code "19") (name "EP_D3") (class "Default")
      (node (ref "DD3") (pin "31") (pinfunction "IO19_31") (pintype "passive"))
      (node (ref "XS1") (pin "17") (pinfunction "17_17") (pintype "passive"))
    )
    (net (code "20") (name "EP_D4") (class "Default")
      (node (ref "DD3") (pin "24") (pinfunction "IO2_24") (pintype "passive"))
      (node (ref "XS1") (pin "18") (pinfunction "18_18") (pintype "passive"))
    )
    (net (code "21") (name "EP_D5") (class "Default")
      (node (ref "DD3") (pin "12") (pinfunction "IO27_12") (pintype "passive"))
      (node (ref "XS1") (pin "19") (pinfunction "19_19") (pintype "passive"))
    )
    (net (code "22") (name "EP_D6") (class "Default")
      (node (ref "DD3") (pin "33") (pinfunction "IO21_33") (pintype "passive"))
      (node (ref "XS1") (pin "20") (pinfunction "20_20") (pintype "passive"))
    )
    (net (code "23") (name "EP_D7") (class "Default")
      (node (ref "DD3") (pin "36") (pinfunction "IO22_36") (pintype "passive"))
      (node (ref "XS1") (pin "21") (pinfunction "21_21") (pintype "passive"))
    )
    (net (code "24") (name "EP_LE") (class "Default")
      (node (ref "DD2") (pin "4") (pinfunction "QP0_4") (pintype "passive"))
      (node (ref "XS1") (pin "11") (pinfunction "11_11") (pintype "passive"))
    )
    (net (code "25") (name "EP_MODE") (class "Default")
      (node (ref "DD2") (pin "12") (pinfunction "QP6_12") (pintype "passive"))
      (node (ref "XS1") (pin "38") (pinfunction "38_38") (pintype "passive"))
    )
    (net (code "26") (name "EP_OE") (class "Default")
      (node (ref "DD2") (pin "11") (pinfunction "QP7_11") (pintype "passive"))
      (node (ref "XS1") (pin "12") (pinfunction "12_12") (pintype "passive"))
    )
    (net (code "27") (name "EP_STH") (class "Default")
      (node (ref "DD3") (pin "11") (pinfunction "IO26_11") (pintype "passive"))
      (node (ref "XS1") (pin "13") (pinfunction "13_13") (pintype "passive"))
    )
    (net (code "28") (name "EP_STV") (class "Default")
      (node (ref "DD2") (pin "14") (pinfunction "QP4_14") (pintype "passive"))
      (node (ref "XS1") (pin "37") (pinfunction "37_37") (pintype "passive"))
    )
    (net (code "29") (name "EP_VCOM") (class "Default")
      (node (ref "DD1") (pin "1") (pinfunction "1OUT_1") (pintype "passive"))
      (node (ref "DD1") (pin "2") (pinfunction "1IN-_2") (pintype "passive"))
      (node (ref "XS1") (pin "24") (pinfunction "24_24") (pintype "passive"))
      (node (ref "XS1") (pin "26") (pinfunction "26_26") (pintype "passive"))
    )
    (net (code "30") (name "GND") (class "Default")
      (node (ref "C1") (pin "1") (pinfunction "A_1") (pintype "passive"))
      (node (ref "C10") (pin "2") (pinfunction "A_2") (pintype "passive"))
      (node (ref "C11") (pin "1") (pinfunction "A_1") (pintype "passive"))
      (node (ref "C12") (pin "1") (pinfunction "A_1") (pintype "passive"))
      (node (ref "C13") (pin "1") (pinfunction "A_1") (pintype "passive"))
      (node (ref "C14") (pin "2") (pinfunction "A_2") (pintype "passive"))
      (node (ref "C17") (pin "1") (pinfunction "A_1") (pintype "passive"))
      (node (ref "C18") (pin "2") (pinfunction "A_2") (pintype "passive"))
      (node (ref "C19") (pin "1") (pinfunction "A_1") (pintype "passive"))
      (node (ref "C2") (pin "2") (pinfunction "A_2") (pintype "passive"))
      (node (ref "C21") (pin "1") (pinfunction "A_1") (pintype "passive"))
      (node (ref "C22") (pin "2") (pinfunction "A_2") (pintype "passive"))
      (node (ref "C24") (pin "2") (pinfunction "A_2") (pintype "passive"))
      (node (ref "C25") (pin "1") (pinfunction "A_1") (pintype "passive"))
      (node (ref "C26") (pin "2") (pinfunction "A_2") (pintype "passive"))
      (node (ref "C27") (pin "2") (pinfunction "A_2") (pintype "passive"))
      (node (ref "C28") (pin "1") (pinfunction "A_1") (pintype "passive"))
      (node (ref "C29") (pin "2") (pinfunction "A_2") (pintype "passive"))
      (node (ref "C3") (pin "1") (pinfunction "A_1") (pintype "passive"))
      (node (ref "C30") (pin "1") (pinfunction "A_1") (pintype "passive"))
      (node (ref "C31") (pin "2") (pinfunction "A_2") (pintype "passive"))
      (node (ref "C32") (pin "2") (pinfunction "A_2") (pintype "passive"))
      (node (ref "C33") (pin "1") (pinfunction "A_1") (pintype "passive"))
      (node (ref "C34") (pin "2") (pinfunction "A_2") (pintype "passive"))
      (node (ref "C35") (pin "2") (pinfunction "A_2") (pintype "passive"))
      (node (ref "C36") (pin "2") (pinfunction "A_2") (pintype "passive"))
      (node (ref "C37") (pin "2") (pinfunction "A_2") (pintype "passive"))
      (node (ref "C38") (pin "2") (pinfunction "A_2") (pintype "passive"))
      (node (ref "C39") (pin "2") (pinfunction "A_2") (pintype "passive"))
      (node (ref "C4") (pin "2") (pinfunction "A_2") (pintype "passive"))
      (node (ref "C40") (pin "2") (pinfunction "A_2") (pintype "passive"))
      (node (ref "C41") (pin "2") (pinfunction "A_2") (pintype "passive"))
      (node (ref "C42") (pin "2") (pinfunction "A_2") (pintype "passive"))
      (node (ref "C43") (pin "2") (pinfunction "A_2") (pintype "passive"))
      (node (ref "C44") (pin "1") (pinfunction "A_1") (pintype "passive"))
      (node (ref "C45") (pin "2") (pinfunction "A_2") (pintype "passive"))
      (node (ref "C46") (pin "2") (pinfunction "A_2") (pintype "passive"))
      (node (ref "C47") (pin "1") (pinfunction "A_1") (pintype "passive"))
      (node (ref "C48") (pin "2") (pinfunction "A_2") (pintype "passive"))
      (node (ref "C5") (pin "2") (pinfunction "A_2") (pintype "passive"))
      (node (ref "C6") (pin "2") (pinfunction "A_2") (pintype "passive"))
      (node (ref "C7") (pin "2") (pinfunction "A_2") (pintype "passive"))
      (node (ref "C8") (pin "2") (pinfunction "A_2") (pintype "passive"))
      (node (ref "C9") (pin "1") (pinfunction "A_1") (pintype "passive"))
      (node (ref "DD10") (pin "1") (pinfunction "GND_1") (pintype "passive"))
      (node (ref "DD10") (pin "14") (pinfunction "GND_14") (pintype "passive"))
      (node (ref "DD10") (pin "15") (pinfunction "GND_15") (pintype "passive"))
      (node (ref "DD10") (pin "2") (pinfunction "GND_2") (pintype "passive"))
      (node (ref "DD10") (pin "3") (pinfunction "GND_3") (pintype "passive"))
      (node (ref "DD10") (pin "4") (pinfunction "GND_4") (pintype "passive"))
      (node (ref "DD10") (pin "7") (pinfunction "GND_7") (pintype "passive"))
      (node (ref "DD11") (pin "2") (pinfunction "GND_2") (pintype "passive"))
      (node (ref "DD2") (pin "8") (pinfunction "GND_8") (pintype "passive"))
      (node (ref "DD3") (pin "1") (pinfunction "GND_1") (pintype "passive"))
      (node (ref "DD3") (pin "15") (pinfunction "GND_15") (pintype "passive"))
      (node (ref "DD3") (pin "38") (pinfunction "GND_38") (pintype "passive"))
      (node (ref "DD3") (pin "39") (pinfunction "GND_39") (pintype "passive"))
      (node (ref "DD4") (pin "2") (pinfunction "VM_2") (pintype "passive"))
      (node (ref "DD4") (pin "3") (pinfunction "VM_3") (pintype "passive"))
      (node (ref "DD4") (pin "4") (pinfunction "VM_4") (pintype "passive"))
      (node (ref "DD5") (pin "3") (pinfunction "GND_3") (pintype "passive"))
      (node (ref "DD5") (pin "7") (pinfunction "PGND_7") (pintype "passive"))
      (node (ref "DD5") (pin "9") (pinfunction "PGND_9") (pintype "passive"))
      (node (ref "DD6") (pin "2") (pinfunction "GND_2") (pintype "passive"))
      (node (ref "DD6") (pin "3") (pinfunction "EN_3") (pintype "passive"))
      (node (ref "DD7") (pin "3") (pinfunction "GND_3") (pintype "passive"))
      (node (ref "DD7") (pin "9") (pinfunction "EP_9") (pintype "passive"))
      (node (ref "DD8") (pin "2") (pinfunction "GND_2") (pintype "passive"))
      (node (ref "DD9") (pin "2") (pinfunction "GND_2") (pintype "passive"))
      (node (ref "R10") (pin "1") (pinfunction "A_1") (pintype "passive"))
      (node (ref "R16") (pin "1") (pinfunction "A_1") (pintype "passive"))
      (node (ref "R17") (pin "2") (pinfunction "B_2") (pintype "passive"))
      (node (ref "R20") (pin "1") (pinfunction "A_1") (pintype "passive"))
      (node (ref "R24") (pin "1") (pinfunction "A_1") (pintype "passive"))
      (node (ref "R27") (pin "1") (pinfunction "A_1") (pintype "passive"))
      (node (ref "R28") (pin "1") (pinfunction "A_1") (pintype "passive"))
      (node (ref "R37") (pin "2") (pinfunction "B_2") (pintype "passive"))
      (node (ref "R38") (pin "2") (pinfunction "B_2") (pintype "passive"))
      (node (ref "R41") (pin "1") (pinfunction "A_1") (pintype "passive"))
      (node (ref "R42") (pin "2") (pinfunction "B_2") (pintype "passive"))
      (node (ref "SB1") (pin "2") (pinfunction "2_2") (pintype "passive"))
      (node (ref "SB2") (pin "2") (pinfunction "2_2") (pintype "passive"))
      (node (ref "SB3") (pin "2") (pinfunction "2_2") (pintype "passive"))
      (node (ref "SB4") (pin "2") (pinfunction "2_2") (pintype "passive"))
      (node (ref "SB5") (pin "2") (pinfunction "2_2") (pintype "passive"))
      (node (ref "VD10") (pin "2") (pinfunction "B_2") (pintype "passive"))
      (node (ref "VD11") (pin "2") (pinfunction "B_2") (pintype "passive"))
      (node (ref "VD3") (pin "2") (pinfunction "B_2") (pintype "passive"))
      (node (ref "VD5") (pin "2") (pinfunction "B_2") (pintype "passive"))
      (node (ref "VR1") (pin "3") (pinfunction "C_3") (pintype "passive"))
      (node (ref "VT4") (pin "2") (pinfunction "B_2") (pintype "passive"))
      (node (ref "X2") (pin "2") (pinfunction "2_2") (pintype "passive"))
      (node (ref "XP1") (pin "4") (pinfunction "4_4") (pintype "passive"))
      (node (ref "XP2") (pin "4") (pinfunction "4_4") (pintype "passive"))
      (node (ref "XP3") (pin "1") (pinfunction "1_1") (pintype "passive"))
      (node (ref "XS1") (pin "28") (pinfunction "28_28") (pintype "passive"))
      (node (ref "XS1") (pin "29") (pinfunction "29_29") (pintype "passive"))
      (node (ref "XS1") (pin "3") (pinfunction "3_3") (pintype "passive"))
      (node (ref "XS1") (pin "30") (pinfunction "30_30") (pintype "passive"))
      (node (ref "XS1") (pin "32") (pinfunction "32_32") (pintype "passive"))
      (node (ref "XS1") (pin "34") (pinfunction "34_34") (pintype "passive"))
      (node (ref "XS1") (pin "35") (pinfunction "35_35") (pintype "passive"))
      (node (ref "XS1") (pin "4") (pinfunction "4_4") (pintype "passive"))
      (node (ref "XS1") (pin "45") (pinfunction "45_45") (pintype "passive"))
      (node (ref "XS1") (pin "46") (pinfunction "46_46") (pintype "passive"))
      (node (ref "XS1") (pin "47") (pinfunction "47_47") (pintype "passive"))
      (node (ref "XS1") (pin "48") (pinfunction "48_48") (pintype "passive"))
      (node (ref "XS1") (pin "6") (pinfunction "6_6") (pintype "passive"))
      (node (ref "XS1") (pin "8") (pinfunction "8_8") (pintype "passive"))
      (node (ref "XS1") (pin "9") (pinfunction "9_9") (pintype "passive"))
    )
    (net (code "31") (name "IO12") (class "Default")
      (node (ref "DD3") (pin "14") (pinfunction "IO12_14") (pintype "passive"))
      (node (ref "XP2") (pin "2") (pinfunction "2_2") (pintype "passive"))
    )
    (net (code "32") (name "IO13") (class "Default")
      (node (ref "C13") (pin "2") (pinfunction "A_2") (pintype "passive"))
      (node (ref "C9") (pin "2") (pinfunction "A_2") (pintype "passive"))
      (node (ref "DD3") (pin "16") (pinfunction "IO13_16") (pintype "passive"))
      (node (ref "DD3") (pin "2") (pinfunction "VDD33_2") (pintype "passive"))
      (node (ref "XP2") (pin "3") (pinfunction "3_3") (pintype "passive"))
    )
    (net (code "33") (name "IO14") (class "Default")
      (node (ref "DD3") (pin "13") (pinfunction "IO14_13") (pintype "passive"))
      (node (ref "XP1") (pin "2") (pinfunction "2_2") (pintype "passive"))
    )
    (net (code "34") (name "IO15") (class "Default")
      (node (ref "DD3") (pin "23") (pinfunction "IO15_23") (pintype "passive"))
      (node (ref "XP1") (pin "3") (pinfunction "3_3") (pintype "passive"))
    )
    (net (code "35") (name "IO34") (class "Default")
      (node (ref "C25") (pin "2") (pinfunction "A_2") (pintype "passive"))
      (node (ref "DD3") (pin "6") (pinfunction "IO34_6") (pintype "passive"))
      (node (ref "R13") (pin "1") (pinfunction "A_1") (pintype "passive"))
      (node (ref "SB2") (pin "1") (pinfunction "1_1") (pintype "passive"))
    )
    (net (code "36") (name "IO35") (class "Default")
      (node (ref "C30") (pin "2") (pinfunction "A_2") (pintype "passive"))
      (node (ref "DD3") (pin "7") (pinfunction "IO35_7") (pintype "passive"))
      (node (ref "R21") (pin "1") (pinfunction "A_1") (pintype "passive"))
      (node (ref "SB3") (pin "1") (pinfunction "1_1") (pintype "passive"))
    )
    (net (code "37") (name "ISP_RX") (class "Default")
      (node (ref "R39") (pin "2") (pinfunction "B_2") (pintype "passive"))
      (node (ref "VT6") (pin "2") (pinfunction "B_2") (pintype "passive"))
    )
    (net (code "38") (name "ISP_TX") (class "Default")
      (node (ref "R40") (pin "2") (pinfunction "B_2") (pintype "passive"))
      (node (ref "VT5") (pin "2") (pinfunction "B_2") (pintype "passive"))
    )
    (net (code "39") (name "NEG_CTRL") (class "Default")
      (node (ref "DD2") (pin "7") (pinfunction "QP3_7") (pintype "passive"))
      (node (ref "XP3") (pin "4") (pinfunction "4_4") (pintype "passive"))
    )
    (net (code "40") (name "Net-(DD1-1IN+)") (class "Default")
      (node (ref "DD1") (pin "3") (pinfunction "1IN+_3") (pintype "passive"))
      (node (ref "VR1") (pin "1") (pinfunction "A_1") (pintype "passive"))
    )
    (net (code "41") (name "Net-(DD4-EPAD)") (class "Default")
      (node (ref "C15") (pin "2") (pinfunction "A_2") (pintype "passive"))
      (node (ref "C18") (pin "1") (pinfunction "A_1") (pintype "passive"))
      (node (ref "DD4") (pin "5") (pinfunction "GND_5") (pintype "passive"))
      (node (ref "DD4") (pin "7") (pinfunction "GND_7") (pintype "passive"))
      (node (ref "DD4") (pin "8") (pinfunction "GND_8") (pintype "passive"))
      (node (ref "DD4") (pin "9") (pinfunction "EPAD_9") (pintype "passive"))
      (node (ref "VT1") (pin "1") (pinfunction "A_1") (pintype "passive"))
    )
    (net (code "42") (name "Net-(DD4-VDD)") (class "Default")
      (node (ref "C15") (pin "1") (pinfunction "A_1") (pintype "passive"))
      (node (ref "DD4") (pin "6") (pinfunction "VDD_6") (pintype "passive"))
      (node (ref "R8") (pin "1") (pinfunction "A_1") (pintype "passive"))
    )
    (net (code "43") (name "Net-(DD5-FB2)") (class "Default")
      (node (ref "C16") (pin "1") (pinfunction "A_1") (pintype "passive"))
      (node (ref "DD5") (pin "5") (pinfunction "FB2_5") (pintype "passive"))
      (node (ref "R17") (pin "1") (pinfunction "A_1") (pintype "passive"))
      (node (ref "R18") (pin "2") (pinfunction "B_2") (pintype "passive"))
    )
    (net (code "44") (name "Net-(DD5-NFB1)") (class "Default")
      (node (ref "C23") (pin "2") (pinfunction "A_2") (pintype "passive"))
      (node (ref "DD5") (pin "1") (pinfunction "NFB1_1") (pintype "passive"))
      (node (ref "R15") (pin "1") (pinfunction "A_1") (pintype "passive"))
      (node (ref "R16") (pin "2") (pinfunction "B_2") (pintype "passive"))
    )
    (net (code "45") (name "Net-(DD5-SW1)") (class "Default")
      (node (ref "C20") (pin "2") (pinfunction "A_2") (pintype "passive"))
      (node (ref "DD5") (pin "10") (pinfunction "SW1_10") (pintype "passive"))
      (node (ref "R4") (pin "2") (pinfunction "B_2") (pintype "passive"))
    )
    (net (code "46") (name "Net-(DD5-SW2)") (class "Default")
      (node (ref "DD5") (pin "6") (pinfunction "SW2_6") (pintype "passive"))
      (node (ref "R7") (pin "2") (pinfunction "B_2") (pintype "passive"))
      (node (ref "VD2") (pin "1") (pinfunction "A_1") (pintype "passive"))
    )
    (net (code "47") (name "Net-(DD5-~{SHDN1})") (class "Default")
      (node (ref "DD5") (pin "2") (pinfunction "~{SHDN1}_2") (pintype "passive"))
      (node (ref "R5") (pin "2") (pinfunction "B_2") (pintype "passive"))
    )
    (net (code "48") (name "Net-(DD5-~{SHDN2})") (class "Default")
      (node (ref "DD5") (pin "4") (pinfunction "~{SHDN2}_4") (pintype "passive"))
      (node (ref "R6") (pin "2") (pinfunction "B_2") (pintype "passive"))
    )
    (net (code "49") (name "Net-(DD6-IN)") (class "Default")
      (node (ref "C17") (pin "2") (pinfunction "A_2") (pintype "passive"))
      (node (ref "C19") (pin "2") (pinfunction "A_2") (pintype "passive"))
      (node (ref "DD6") (pin "1") (pinfunction "IN_1") (pintype "passive"))
      (node (ref "R10") (pin "2") (pinfunction "B_2") (pintype "passive"))
      (node (ref "R12") (pin "1") (pinfunction "A_1") (pintype "passive"))
      (node (ref "R9") (pin "2") (pinfunction "B_2") (pintype "passive"))
      (node (ref "VT2") (pin "1") (pinfunction "A_1") (pintype "passive"))
    )
    (net (code "50") (name "Net-(DD7-CHRG)") (class "Default")
      (node (ref "DD7") (pin "6") (pinfunction "CHRG_6") (pintype "passive"))
      (node (ref "VD9") (pin "2") (pinfunction "B_2") (pintype "passive"))
    )
    (net (code "51") (name "Net-(DD7-CT)") (class "Default")
      (node (ref "C31") (pin "1") (pinfunction "A_1") (pintype "passive"))
      (node (ref "DD7") (pin "4") (pinfunction "CT_4") (pintype "passive"))
    )
    (net (code "52") (name "Net-(DD7-Iprog)") (class "Default")
      (node (ref "DD7") (pin "5") (pinfunction "Iprog_5") (pintype "passive"))
      (node (ref "R28") (pin "2") (pinfunction "B_2") (pintype "passive"))
    )
    (net (code "53") (name "Net-(DD7-STDB)") (class "Default")
      (node (ref "DD7") (pin "7") (pinfunction "STDB_7") (pintype "passive"))
      (node (ref "VD8") (pin "2") (pinfunction "B_2") (pintype "passive"))
    )
    (net (code "54") (name "Net-(DD7-Vprog)") (class "Default")
      (node (ref "DD7") (pin "2") (pinfunction "Vprog_2") (pintype "passive"))
      (node (ref "R19") (pin "1") (pinfunction "A_1") (pintype "passive"))
      (node (ref "R20") (pin "2") (pinfunction "B_2") (pintype "passive"))
    )
    (net (code "55") (name "Net-(DD11-D+)") (class "Default")
      (node (ref "DD11") (pin "3") (pinfunction "D+_3") (pintype "passive"))
      (node (ref "R35") (pin "2") (pinfunction "B_2") (pintype "passive"))
    )
    (net (code "56") (name "Net-(DD11-D-)") (class "Default")
      (node (ref "DD11") (pin "4") (pinfunction "D-_4") (pintype "passive"))
      (node (ref "R34") (pin "2") (pinfunction "B_2") (pintype "passive"))
    )
    (net (code "57") (name "Net-(DD11-RST)") (class "Default")
      (node (ref "C45") (pin "1") (pinfunction "A_1") (pintype "passive"))
      (node (ref "DD11") (pin "9") (pinfunction "RST_9") (pintype "passive"))
      (node (ref "R36") (pin "2") (pinfunction "B_2") (pintype "passive"))
    )
    (net (code "58") (name "Net-(DD11-RXD)") (class "Default")
      (node (ref "DD11") (pin "20") (pinfunction "RXD_20") (pintype "passive"))
      (node (ref "R39") (pin "1") (pinfunction "A_1") (pintype "passive"))
    )
    (net (code "59") (name "Net-(DD11-TXD)") (class "Default")
      (node (ref "DD11") (pin "21") (pinfunction "TXD_21") (pintype "passive"))
      (node (ref "R40") (pin "1") (pinfunction "A_1") (pintype "passive"))
    )
    (net (code "60") (name "Net-(DD11-VPP)") (class "Default")
      (node (ref "C47") (pin "2") (pinfunction "A_2") (pintype "passive"))
      (node (ref "DD11") (pin "16") (pinfunction "VPP_16") (pintype "passive"))
    )
    (net (code "61") (name "Net-(R1-A)") (class "Default")
      (node (ref "R1") (pin "1") (pinfunction "A_1") (pintype "passive"))
      (node (ref "VR1") (pin "2") (pinfunction "B_2") (pintype "passive"))
    )
    (net (code "62") (name "Net-(R2-A)") (class "Default")
      (node (ref "R2") (pin "1") (pinfunction "A_1") (pintype "passive"))
      (node (ref "VT1") (pin "2") (pinfunction "B_2") (pintype "passive"))
      (node (ref "X1") (pin "2") (pinfunction "2_2") (pintype "passive"))
    )
    (net (code "63") (name "Net-(R2-B)") (class "Default")
      (node (ref "R2") (pin "2") (pinfunction "B_2") (pintype "passive"))
      (node (ref "VD1") (pin "1") (pinfunction "A_1") (pintype "passive"))
    )
    (net (code "64") (name "Net-(R3-A)") (class "Default")
      (node (ref "R3") (pin "1") (pinfunction "A_1") (pintype "passive"))
      (node (ref "VT1") (pin "3") (pinfunction "C_3") (pintype "passive"))
    )
    (net (code "65") (name "Net-(R12-B)") (class "Default")
      (node (ref "R12") (pin "2") (pinfunction "B_2") (pintype "passive"))
      (node (ref "R14") (pin "1") (pinfunction "A_1") (pintype "passive"))
      (node (ref "VT2") (pin "3") (pinfunction "C_3") (pintype "passive"))
      (node (ref "VT3") (pin "3") (pinfunction "C_3") (pintype "passive"))
    )
    (net (code "66") (name "Net-(R14-B)") (class "Default")
      (node (ref "R14") (pin "2") (pinfunction "B_2") (pintype "passive"))
      (node (ref "VT4") (pin "1") (pinfunction "A_1") (pintype "passive"))
    )
    (net (code "67") (name "Net-(R22-A)") (class "Default")
      (node (ref "R22") (pin "1") (pinfunction "A_1") (pintype "passive"))
      (node (ref "VT4") (pin "3") (pinfunction "C_3") (pintype "passive"))
    )
    (net (code "68") (name "Net-(R22-B)") (class "Default")
      (node (ref "R22") (pin "2") (pinfunction "B_2") (pintype "passive"))
      (node (ref "R24") (pin "2") (pinfunction "B_2") (pintype "passive"))
      (node (ref "VD6") (pin "2") (pinfunction "2_2") (pintype "passive"))
      (node (ref "VD7") (pin "2") (pinfunction "2_2") (pintype "passive"))
    )
    (net (code "69") (name "Net-(R23-B)") (class "Default")
      (node (ref "R23") (pin "2") (pinfunction "B_2") (pintype "passive"))
      (node (ref "VD5") (pin "1") (pinfunction "A_1") (pintype "passive"))
    )
    (net (code "70") (name "Net-(R29-A)") (class "Default")
      (node (ref "R29") (pin "1") (pinfunction "A_1") (pintype "passive"))
      (node (ref "VD8") (pin "1") (pinfunction "A_1") (pintype "passive"))
    )
    (net (code "71") (name "Net-(R30-A)") (class "Default")
      (node (ref "R30") (pin "1") (pinfunction "A_1") (pintype "passive"))
      (node (ref "VD9") (pin "1") (pinfunction "A_1") (pintype "passive"))
    )
    (net (code "72") (name "Net-(R31-A)") (class "Default")
      (node (ref "C36") (pin "1") (pinfunction "A_1") (pintype "passive"))
      (node (ref "R31") (pin "1") (pinfunction "A_1") (pintype "passive"))
    )
    (net (code "73") (name "Net-(R32-A)") (class "Default")
      (node (ref "R32") (pin "1") (pinfunction "A_1") (pintype "passive"))
      (node (ref "VT5") (pin "3") (pinfunction "C_3") (pintype "passive"))
    )
    (net (code "74") (name "Net-(R33-A)") (class "Default")
      (node (ref "R33") (pin "1") (pinfunction "A_1") (pintype "passive"))
      (node (ref "VT6") (pin "3") (pinfunction "C_3") (pintype "passive"))
    )
    (net (code "75") (name "Net-(VD3-A)") (class "Default")
      (node (ref "C20") (pin "1") (pinfunction "A_1") (pintype "passive"))
      (node (ref "VD3") (pin "1") (pinfunction "A_1") (pintype "passive"))
      (node (ref "VD4") (pin "2") (pinfunction "B_2") (pintype "passive"))
    )
    (net (code "76") (name "POS_CTRL") (class "Default")
      (node (ref "DD2") (pin "6") (pinfunction "QP2_6") (pintype "passive"))
      (node (ref "XP3") (pin "3") (pinfunction "3_3") (pintype "passive"))
    )
    (net (code "77") (name "PWR_EN") (class "Default")
      (node (ref "DD2") (pin "13") (pinfunction "QP5_13") (pintype "passive"))
      (node (ref "VD7") (pin "1") (pinfunction "1_1") (pintype "passive"))
    )
    (net (code "78") (name "RTS") (class "Default")
      (node (ref "DD11") (pin "19") (pinfunction "RTS_19") (pintype "passive"))
      (node (ref "DD12") (pin "1") (pinfunction "E1_1") (pintype "passive"))
      (node (ref "DD12") (pin "5") (pinfunction "B2_5") (pintype "passive"))
    )
    (net (code "79") (name "SENSOR_VN") (class "Default")
      (node (ref "C21") (pin "2") (pinfunction "A_2") (pintype "passive"))
      (node (ref "DD3") (pin "5") (pinfunction "S_VN_5") (pintype "passive"))
      (node (ref "R11") (pin "1") (pinfunction "A_1") (pintype "passive"))
      (node (ref "SB1") (pin "1") (pinfunction "1_1") (pintype "passive"))
    )
    (net (code "80") (name "SMPS_CTRL") (class "Default")
      (node (ref "DD2") (pin "5") (pinfunction "QP1_5") (pintype "passive"))
      (node (ref "XP3") (pin "2") (pinfunction "2_2") (pintype "passive"))
    )
    (net (code "81") (name "STR_IO0") (class "Default")
      (node (ref "DD12") (pin "3") (pinfunction "C2_3") (pintype "passive"))
      (node (ref "DD2") (pin "1") (pinfunction "STR_1") (pintype "passive"))
      (node (ref "DD3") (pin "25") (pinfunction "IO0_25") (pintype "passive"))
      (node (ref "SB5") (pin "1") (pinfunction "1_1") (pintype "passive"))
    )
    (net (code "82") (name "UAR0_RX") (class "Default")
      (node (ref "DD3") (pin "34") (pinfunction "RXD0_34") (pintype "passive"))
      (node (ref "VT5") (pin "1") (pinfunction "A_1") (pintype "passive"))
    )
    (net (code "83") (name "UAR0_TX") (class "Default")
      (node (ref "DD3") (pin "35") (pinfunction "TXD0_35") (pintype "passive"))
      (node (ref "VT6") (pin "1") (pinfunction "A_1") (pintype "passive"))
    )
    (net (code "84") (name "USB1_N") (class "Default")
      (node (ref "C42") (pin "1") (pinfunction "A_1") (pintype "passive"))
      (node (ref "DD10") (pin "11") (pinfunction "DN1-_11") (pintype "passive"))
      (node (ref "DD10") (pin "19") (pinfunction "DN-_19") (pintype "passive"))
      (node (ref "R35") (pin "1") (pinfunction "A_1") (pintype "passive"))
      (node (ref "VD10") (pin "1") (pinfunction "A_1") (pintype "passive"))
    )
    (net (code "85") (name "USB1_P") (class "Default")
      (node (ref "C41") (pin "1") (pinfunction "A_1") (pintype "passive"))
      (node (ref "DD10") (pin "10") (pinfunction "DP1+_10") (pintype "passive"))
      (node (ref "DD10") (pin "18") (pinfunction "DP+_18") (pintype "passive"))
      (node (ref "R34") (pin "1") (pinfunction "A_1") (pintype "passive"))
      (node (ref "VD11") (pin "1") (pinfunction "A_1") (pintype "passive"))
    )
    (net (code "86") (name "VBAT") (class "Default")
      (node (ref "C22") (pin "1") (pinfunction "A_1") (pintype "passive"))
      (node (ref "C24") (pin "1") (pinfunction "A_1") (pintype "passive"))
      (node (ref "C46") (pin "1") (pinfunction "A_1") (pintype "passive"))
      (node (ref "C48") (pin "1") (pinfunction "A_1") (pintype "passive"))
      (node (ref "DD7") (pin "1") (pinfunction "BAT_1") (pintype "passive"))
      (node (ref "R19") (pin "2") (pinfunction "B_2") (pintype "passive"))
      (node (ref "R3") (pin "2") (pinfunction "B_2") (pintype "passive"))
      (node (ref "R41") (pin "2") (pinfunction "B_2") (pintype "passive"))
      (node (ref "R8") (pin "2") (pinfunction "B_2") (pintype "passive"))
      (node (ref "VD1") (pin "2") (pinfunction "B_2") (pintype "passive"))
      (node (ref "VT7") (pin "1") (pinfunction "A_1") (pintype "passive"))
      (node (ref "X1") (pin "1") (pinfunction "1_1") (pintype "passive"))
      (node (ref "X2") (pin "1") (pinfunction "1_1") (pintype "passive"))
    )
    (net (code "87") (name "VBUS") (class "Default")
      (node (ref "C39") (pin "1") (pinfunction "A_1") (pintype "passive"))
      (node (ref "C40") (pin "1") (pinfunction "A_1") (pintype "passive"))
      (node (ref "C44") (pin "2") (pinfunction "A_2") (pintype "passive"))
      (node (ref "DD10") (pin "13") (pinfunction "UBUS2_13") (pintype "passive"))
      (node (ref "DD10") (pin "16") (pinfunction "PWR_16") (pintype "passive"))
      (node (ref "DD10") (pin "8") (pinfunction "UBUS1_8") (pintype "passive"))
      (node (ref "DD11") (pin "7") (pinfunction "REGIN_7") (pintype "passive"))
      (node (ref "DD11") (pin "8") (pinfunction "VBUS_8") (pintype "passive"))
      (node (ref "DD7") (pin "8") (pinfunction "VDD_8") (pintype "passive"))
      (node (ref "R29") (pin "2") (pinfunction "B_2") (pintype "passive"))
      (node (ref "R30") (pin "2") (pinfunction "B_2") (pintype "passive"))
      (node (ref "R31") (pin "2") (pinfunction "B_2") (pintype "passive"))
      (node (ref "R42") (pin "1") (pinfunction "A_1") (pintype "passive"))
      (node (ref "VD12") (pin "1") (pinfunction "A_1") (pintype "passive"))
      (node (ref "VD6") (pin "1") (pinfunction "1_1") (pintype "passive"))
      (node (ref "VT7") (pin "3") (pinfunction "C_3") (pintype "passive"))
    )
    (net (code "88") (name "VDD3V3") (class "Default")
      (node (ref "C11") (pin "2") (pinfunction "A_2") (pintype "passive"))
      (node (ref "C12") (pin "2") (pinfunction "A_2") (pintype "passive"))
      (node (ref "DD2") (pin "15") (pinfunction "OE_15") (pintype "passive"))
      (node (ref "DD2") (pin "16") (pinfunction "VCC_16") (pintype "passive"))
      (node (ref "R11") (pin "2") (pinfunction "B_2") (pintype "passive"))
      (node (ref "R13") (pin "2") (pinfunction "B_2") (pintype "passive"))
      (node (ref "R21") (pin "2") (pinfunction "B_2") (pintype "passive"))
      (node (ref "R25") (pin "2") (pinfunction "B_2") (pintype "passive"))
    )
    (net (code "89") (name "VDDV3") (class "Default")
      (node (ref "C26") (pin "1") (pinfunction "A_1") (pintype "passive"))
      (node (ref "C29") (pin "1") (pinfunction "A_1") (pintype "passive"))
      (node (ref "DD6") (pin "5") (pinfunction "OUT_5") (pintype "passive"))
      (node (ref "VT3") (pin "1") (pinfunction "A_1") (pintype "passive"))
    )
    (net (code "90") (name "VDD_UART") (class "Default")
      (node (ref "C37") (pin "1") (pinfunction "A_1") (pintype "passive"))
      (node (ref "DD11") (pin "5") (pinfunction "VIO_5") (pintype "passive"))
      (node (ref "DD11") (pin "6") (pinfunction "VDD_6") (pintype "passive"))
      (node (ref "R32") (pin "2") (pinfunction "B_2") (pintype "passive"))
      (node (ref "R33") (pin "2") (pinfunction "B_2") (pintype "passive"))
      (node (ref "R36") (pin "1") (pinfunction "A_1") (pintype "passive"))
      (node (ref "R37") (pin "1") (pinfunction "A_1") (pintype "passive"))
    )
    (net (code "91") (name "unconnected-(DD1-2IN+-Pad5)") (class "Default")
      (node (ref "DD1") (pin "5") (pinfunction "2IN+_5") (pintype "passive"))
    )
    (net (code "92") (name "unconnected-(DD1-2IN--Pad6)") (class "Default")
      (node (ref "DD1") (pin "6") (pinfunction "2IN-_6") (pintype "passive"))
    )
    (net (code "93") (name "unconnected-(DD1-2OUT-Pad7)") (class "Default")
      (node (ref "DD1") (pin "7") (pinfunction "2OUT_7") (pintype "passive"))
    )
    (net (code "94") (name "unconnected-(DD2-QS1-Pad9)") (class "Default")
      (node (ref "DD2") (pin "9") (pinfunction "QS1_9") (pintype "passive"))
    )
    (net (code "95") (name "unconnected-(DD2-QS2-Pad10)") (class "Default")
      (node (ref "DD2") (pin "10") (pinfunction "QS2_10") (pintype "passive"))
    )
    (net (code "96") (name "unconnected-(DD3-CLK-Pad20)") (class "Default")
      (node (ref "DD3") (pin "20") (pinfunction "CLK_20") (pintype "passive"))
    )
    (net (code "97") (name "unconnected-(DD3-CMD-Pad19)") (class "Default")
      (node (ref "DD3") (pin "19") (pinfunction "CMD_19") (pintype "passive"))
    )
    (net (code "98") (name "unconnected-(DD3-NC-Pad27)") (class "Default")
      (node (ref "DD3") (pin "27") (pinfunction "NC_27") (pintype "passive"))
    )
    (net (code "99") (name "unconnected-(DD3-NC-Pad28)") (class "Default")
      (node (ref "DD3") (pin "28") (pinfunction "NC_28") (pintype "passive"))
    )
    (net (code "100") (name "unconnected-(DD3-NC-Pad32)") (class "Default")
      (node (ref "DD3") (pin "32") (pinfunction "NC_32") (pintype "passive"))
    )
    (net (code "101") (name "unconnected-(DD3-SD0-Pad21)") (class "Default")
      (node (ref "DD3") (pin "21") (pinfunction "SD0_21") (pintype "passive"))
    )
    (net (code "102") (name "unconnected-(DD3-SD1-Pad22)") (class "Default")
      (node (ref "DD3") (pin "22") (pinfunction "SD1_22") (pintype "passive"))
    )
    (net (code "103") (name "unconnected-(DD3-SD2-Pad17)") (class "Default")
      (node (ref "DD3") (pin "17") (pinfunction "SD2_17") (pintype "passive"))
    )
    (net (code "104") (name "unconnected-(DD3-SD3-Pad18)") (class "Default")
      (node (ref "DD3") (pin "18") (pinfunction "SD3_18") (pintype "passive"))
    )
    (net (code "105") (name "unconnected-(DD4-NC-Pad1)") (class "Default")
      (node (ref "DD4") (pin "1") (pinfunction "NC_1") (pintype "passive"))
    )
    (net (code "106") (name "unconnected-(DD6-NC-Pad4)") (class "Default")
      (node (ref "DD6") (pin "4") (pinfunction "NC_4") (pintype "passive"))
    )
    (net (code "107") (name "unconnected-(DD10-GND-Pad22)") (class "Default")
      (node (ref "DD10") (pin "22") (pinfunction "GND_22") (pintype "passive"))
    )
    (net (code "108") (name "unconnected-(DD10-NC-Pad5)") (class "Default")
      (node (ref "DD10") (pin "5") (pinfunction "NC_5") (pintype "passive"))
    )
    (net (code "109") (name "unconnected-(DD10-NC-Pad6)") (class "Default")
      (node (ref "DD10") (pin "6") (pinfunction "NC_6") (pintype "passive"))
    )
    (net (code "110") (name "unconnected-(DD10-PWR1-Pad21)") (class "Default")
      (node (ref "DD10") (pin "21") (pinfunction "PWR1_21") (pintype "passive"))
    )
    (net (code "111") (name "unconnected-(DD10-SUB1-Pad12)") (class "Default")
      (node (ref "DD10") (pin "12") (pinfunction "SUB1_12") (pintype "passive"))
    )
    (net (code "112") (name "unconnected-(DD10-VCONN-Pad17)") (class "Default")
      (node (ref "DD10") (pin "17") (pinfunction "VCONN_17") (pintype "passive"))
    )
    (net (code "113") (name "unconnected-(DD11-CTS-Pad18)") (class "Default")
      (node (ref "DD11") (pin "18") (pinfunction "CTS_18") (pintype "passive"))
    )
    (net (code "114") (name "unconnected-(DD11-DCD-Pad24)") (class "Default")
      (node (ref "DD11") (pin "24") (pinfunction "DCD_24") (pintype "passive"))
    )
    (net (code "115") (name "unconnected-(DD11-DSR-Pad22)") (class "Default")
      (node (ref "DD11") (pin "22") (pinfunction "DSR_22") (pintype "passive"))
    )
    (net (code "116") (name "unconnected-(DD11-GPIO0-Pad14)") (class "Default")
      (node (ref "DD11") (pin "14") (pinfunction "GPIO0_14") (pintype "passive"))
    )
    (net (code "117") (name "unconnected-(DD11-GPIO1-Pad13)") (class "Default")
      (node (ref "DD11") (pin "13") (pinfunction "GPIO1_13") (pintype "passive"))
    )
    (net (code "118") (name "unconnected-(DD11-GPIO2-Pad12)") (class "Default")
      (node (ref "DD11") (pin "12") (pinfunction "GPIO2_12") (pintype "passive"))
    )
    (net (code "119") (name "unconnected-(DD11-GPIO3-Pad11)") (class "Default")
      (node (ref "DD11") (pin "11") (pinfunction "GPIO3_11") (pintype "passive"))
    )
    (net (code "120") (name "unconnected-(DD11-NC-Pad10)") (class "Default")
      (node (ref "DD11") (pin "10") (pinfunction "NC_10") (pintype "passive"))
    )
    (net (code "121") (name "unconnected-(DD11-R1-Pad1)") (class "Default")
      (node (ref "DD11") (pin "1") (pinfunction "R1_1") (pintype "passive"))
    )
    (net (code "122") (name "unconnected-(DD11-S_HIGH-Pad17)") (class "Default")
      (node (ref "DD11") (pin "17") (pinfunction "S_HIGH_17") (pintype "passive"))
    )
    (net (code "123") (name "unconnected-(DD11-S_LOW-Pad15)") (class "Default")
      (node (ref "DD11") (pin "15") (pinfunction "S_LOW_15") (pintype "passive"))
    )
    (net (code "124") (name "unconnected-(XS1-Pad5)") (class "Default")
      (node (ref "XS1") (pin "5") (pinfunction "5_5") (pintype "passive"))
    )
    (net (code "125") (name "unconnected-(XS1-Pad22)") (class "Default")
      (node (ref "XS1") (pin "22") (pinfunction "22_22") (pintype "passive"))
    )
    (net (code "126") (name "unconnected-(XS1-Pad39)") (class "Default")
      (node (ref "XS1") (pin "39") (pinfunction "39_39") (pintype "passive"))
    )
    (net (code "127") (name "unconnected-(XS1-Pad40)") (class "Default")
      (node (ref "XS1") (pin "40") (pinfunction "40_40") (pintype "passive"))
    )
    (net (code "128") (name "unconnected-(XS1-Pad41)") (class "Default")
      (node (ref "XS1") (pin "41") (pinfunction "41_41") (pintype "passive"))
    )
    (net (code "129") (name "unconnected-(XS1-Pad42)") (class "Default")
      (node (ref "XS1") (pin "42") (pinfunction "42_42") (pintype "passive"))
    )
    (net (code "130") (name "unconnected-(XS1-Pad43)") (class "Default")
      (node (ref "XS1") (pin "43") (pinfunction "43_43") (pintype "passive"))
    )
    (net (code "131") (name "unconnected-(XS1-Pad44)") (class "Default")
      (node (ref "XS1") (pin "44") (pinfunction "44_44") (pintype "passive"))
    )
  )
)
